# MCU.net
KiCad netlist of a schematic drawn in Altium Designer
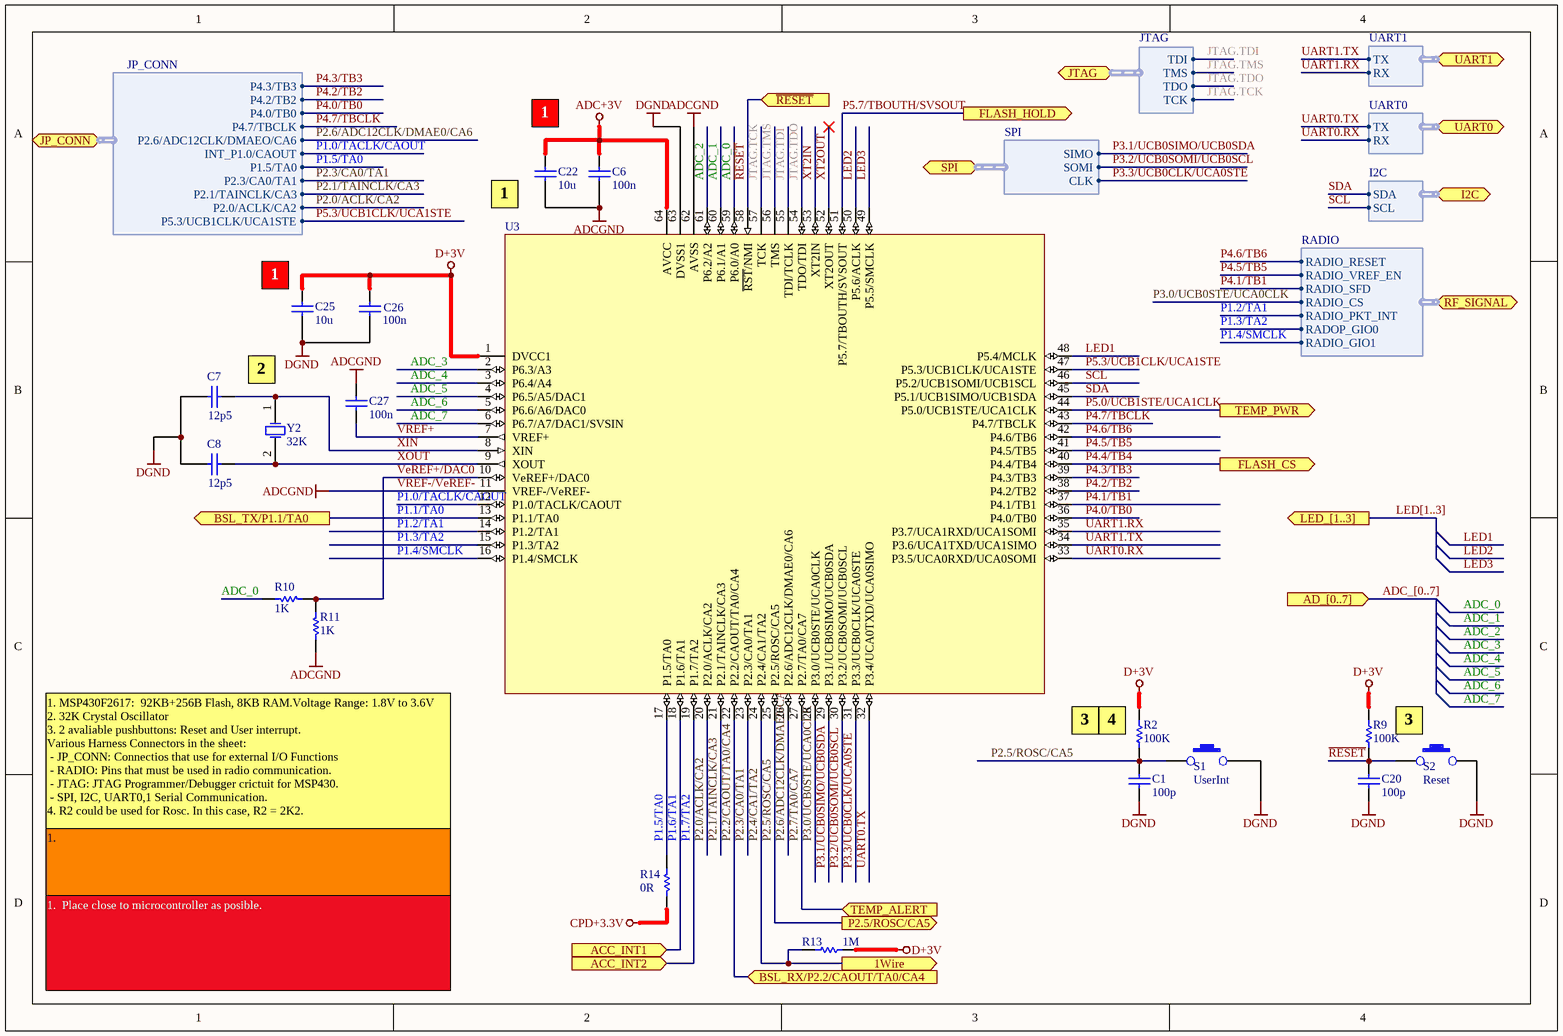
[diagram p0: MCU.SchDoc]

(export (version "E")
  (design (tool "Eeschema 10.0.6"))
  (components
    (comp (ref "C1")
      (value "100p")
      (footprint "CC-0402-AL")
      (description "Capacitor (Semiconductor SIM Model)")
      (fields (field (name "Comment") "Cap Semi"))
      (libsource (lib "Z1_Project") (part "Cap Semi"))
    )
    (comp (ref "C6")
      (value "100n")
      (footprint "CC-0402-AL")
      (description "Capacitor (Semiconductor SIM Model)")
      (fields (field (name "Comment") "Cap Semi"))
      (libsource (lib "Z1_Project") (part "Cap Semi"))
    )
    (comp (ref "C7")
      (value "12p5")
      (footprint "CC-0402-AL")
      (description "Capacitor (Semiconductor SIM Model)")
      (fields (field (name "Comment") "Cap Semi"))
      (libsource (lib "Z1_Project") (part "Cap Semi"))
    )
    (comp (ref "C8")
      (value "12p5")
      (footprint "CC-0402-AL")
      (description "Capacitor (Semiconductor SIM Model)")
      (fields (field (name "Comment") "Cap Semi"))
      (libsource (lib "Z1_Project") (part "Cap Semi"))
    )
    (comp (ref "C20")
      (value "100p")
      (footprint "CC-0402-AL")
      (description "Capacitor (Semiconductor SIM Model)")
      (fields (field (name "Comment") "Cap Semi"))
      (libsource (lib "Z1_Project") (part "Cap Semi"))
    )
    (comp (ref "C22")
      (value "10u")
      (footprint "CC1608-0603")
      (description "CAP CER 10UF 6.3V X5R 0603")
      (fields (field (name "Comment") "Cap Semi"))
      (libsource (lib "Z1_Project") (part "Cap Semi"))
    )
    (comp (ref "C25")
      (value "10u")
      (footprint "CC1608-0603")
      (description "CAP CER 10UF 6.3V X5R 0603")
      (fields (field (name "Comment") "Cap Semi"))
      (libsource (lib "Z1_Project") (part "Cap Semi"))
    )
    (comp (ref "C26")
      (value "100n")
      (footprint "CC-0402-AL")
      (description "Capacitor (Semiconductor SIM Model)")
      (fields (field (name "Comment") "Cap Semi"))
      (libsource (lib "Z1_Project") (part "Cap Semi"))
    )
    (comp (ref "C27")
      (value "100n")
      (footprint "CC-0402-AL")
      (description "Capacitor (Semiconductor SIM Model)")
      (fields (field (name "Comment") "Cap Semi"))
      (libsource (lib "Z1_Project") (part "Cap Semi"))
    )
    (comp (ref "R2")
      (value "100K")
      (footprint "CR1005-0402")
      (description "Semiconductor Resistor")
      (fields (field (name "MANUFACTURER") "Generic Components") (field (name "Comment") "Res Semi"))
      (libsource (lib "Z1_Project") (part "Res Semi"))
    )
    (comp (ref "R9")
      (value "100K")
      (footprint "CR-0402-AL")
      (description "Semiconductor Resistor")
      (fields (field (name "Comment") "Res Semi"))
      (libsource (lib "Z1_Project") (part "Res Semi"))
    )
    (comp (ref "R10")
      (value "1K")
      (footprint "CR-0402-AL")
      (description "Semiconductor Resistor")
      (fields (field (name "Comment") "Res Semi"))
      (libsource (lib "Z1_Project") (part "Res Semi"))
    )
    (comp (ref "R11")
      (value "1K")
      (footprint "CR-0402-AL")
      (description "Semiconductor Resistor")
      (fields (field (name "Comment") "Res Semi"))
      (libsource (lib "Z1_Project") (part "Res Semi"))
    )
    (comp (ref "R13")
      (value "1M")
      (footprint "CR-0402-AL")
      (description "Semiconductor Resistor")
      (fields (field (name "Comment") "Res Semi"))
      (libsource (lib "Z1_Project") (part "Res Semi"))
    )
    (comp (ref "R14")
      (value "0R")
      (footprint "CR-0402-AL")
      (description "Semiconductor Resistor")
      (fields (field (name "Comment") "Res Semi"))
      (libsource (lib "Z1_Project") (part "Res Semi"))
    )
    (comp (ref "S1")
      (value "UserInt")
      (footprint "B3U-1000P")
      (description "Ultra-small Tactile Switch")
      (libsource (lib "Z1_Project") (part "B3U-1000P"))
    )
    (comp (ref "S2")
      (value "Reset")
      (footprint "B3U-1000P")
      (description "Ultra-small Tactile Switch")
      (libsource (lib "Z1_Project") (part "B3U-1000P"))
    )
    (comp (ref "U3")
      (value "MSP430F2617TPMR")
      (footprint "F-QFP10x10-G64/N")
      (description "MSP430F2617TPMR MICROCONTROLLER")
      (libsource (lib "Z1_Project") (part "MSP430F2617TPMR"))
    )
    (comp (ref "Y2")
      (value "32K")
      (footprint "ABS07-32.768KHZ-7-T")
      (description "Crystal Oscillator")
      (fields (field (name "MANUFACTURER") "Generic Components"))
      (libsource (lib "Z1_Project") (part "XTAL"))
    )
  )
  (nets
    (net (code "8") (name "/ADC_0") (class "Default")
      (node (ref "R10") (pin "2") (pinfunction "2_2") (pintype "passive"))
      (node (ref "U3") (pin "59") (pinfunction "P6.0/A0_59") (pintype "bidirectional"))
    )
    (net (code "9") (name "/ADC_1") (class "Default")
      (node (ref "U3") (pin "60") (pinfunction "P6.1/A1_60") (pintype "bidirectional"))
    )
    (net (code "10") (name "/ADC_2") (class "Default")
      (node (ref "U3") (pin "61") (pinfunction "P6.2/A2_61") (pintype "bidirectional"))
    )
    (net (code "11") (name "/ADC_3") (class "Default")
      (node (ref "U3") (pin "2") (pinfunction "P6.3/A3_2") (pintype "bidirectional"))
    )
    (net (code "12") (name "/ADC_4") (class "Default")
      (node (ref "U3") (pin "3") (pinfunction "P6.4/A4_3") (pintype "bidirectional"))
    )
    (net (code "13") (name "/ADC_5") (class "Default")
      (node (ref "U3") (pin "4") (pinfunction "P6.5/A5/DAC1_4") (pintype "bidirectional"))
    )
    (net (code "14") (name "/ADC_6") (class "Default")
      (node (ref "U3") (pin "5") (pinfunction "P6.6/A6/DAC0_5") (pintype "bidirectional"))
    )
    (net (code "15") (name "/ADC_7") (class "Default")
      (node (ref "U3") (pin "6") (pinfunction "P6.7/A7/DAC1/SVSIN_6") (pintype "bidirectional"))
    )
    (net (code "17") (name "/JTAG.TCK") (class "Default")
      (node (ref "U3") (pin "57") (pinfunction "TCK_57") (pintype "passive"))
    )
    (net (code "18") (name "/JTAG.TDI") (class "Default")
      (node (ref "U3") (pin "55") (pinfunction "TDI/TCLK_55") (pintype "passive"))
    )
    (net (code "19") (name "/JTAG.TDO") (class "Default")
      (node (ref "U3") (pin "54") (pinfunction "TDO/TDI_54") (pintype "bidirectional"))
    )
    (net (code "20") (name "/JTAG.TMS") (class "Default")
      (node (ref "U3") (pin "56") (pinfunction "TMS_56") (pintype "passive"))
    )
    (net (code "21") (name "/LED1") (class "Default")
      (node (ref "U3") (pin "48") (pinfunction "P5.4/MCLK_48") (pintype "bidirectional"))
    )
    (net (code "22") (name "/LED2") (class "Default")
      (node (ref "U3") (pin "50") (pinfunction "P5.6/ACLK_50") (pintype "bidirectional"))
    )
    (net (code "23") (name "/LED3") (class "Default")
      (node (ref "U3") (pin "49") (pinfunction "P5.5/SMCLK_49") (pintype "bidirectional"))
    )
    (net (code "25") (name "/P1.0{slash}TACLK{slash}CAOUT") (class "Default")
      (node (ref "U3") (pin "12") (pinfunction "P1.0/TACLK/CAOUT_12") (pintype "bidirectional"))
    )
    (net (code "26") (name "/P1.1{slash}TA0") (class "Default")
      (node (ref "U3") (pin "13") (pinfunction "P1.1/TA0_13") (pintype "bidirectional"))
    )
    (net (code "27") (name "/P1.2{slash}TA1") (class "Default")
      (node (ref "U3") (pin "14") (pinfunction "P1.2/TA1_14") (pintype "bidirectional"))
    )
    (net (code "28") (name "/P1.3{slash}TA2") (class "Default")
      (node (ref "U3") (pin "15") (pinfunction "P1.3/TA2_15") (pintype "bidirectional"))
    )
    (net (code "29") (name "/P1.4{slash}SMCLK") (class "Default")
      (node (ref "U3") (pin "16") (pinfunction "P1.4/SMCLK_16") (pintype "bidirectional"))
    )
    (net (code "30") (name "/P1.5{slash}TA0") (class "Default")
      (node (ref "R14") (pin "2") (pinfunction "2_2") (pintype "passive"))
      (node (ref "U3") (pin "17") (pinfunction "P1.5/TA0_17") (pintype "bidirectional"))
    )
    (net (code "31") (name "/P1.6{slash}TA1") (class "Default")
      (node (ref "U3") (pin "18") (pinfunction "P1.6/TA1_18") (pintype "bidirectional"))
    )
    (net (code "32") (name "/P1.7{slash}TA2") (class "Default")
      (node (ref "U3") (pin "19") (pinfunction "P1.7/TA2_19") (pintype "bidirectional"))
    )
    (net (code "33") (name "/P2.0{slash}ACLK{slash}CA2") (class "Default")
      (node (ref "U3") (pin "20") (pinfunction "P2.0/ACLK/CA2_20") (pintype "bidirectional"))
    )
    (net (code "34") (name "/P2.1{slash}TAINCLK{slash}CA3") (class "Default")
      (node (ref "U3") (pin "21") (pinfunction "P2.1/TAINCLK/CA3_21") (pintype "bidirectional"))
    )
    (net (code "35") (name "/P2.2{slash}CAOUT{slash}TA0{slash}CA4") (class "Default")
      (node (ref "U3") (pin "22") (pinfunction "P2.2/CAOUT/TA0/CA4_22") (pintype "bidirectional"))
    )
    (net (code "36") (name "/P2.3{slash}CA0{slash}TA1") (class "Default")
      (node (ref "U3") (pin "23") (pinfunction "P2.3/CA0/TA1_23") (pintype "bidirectional"))
    )
    (net (code "37") (name "/P2.4{slash}CA1{slash}TA2") (class "Default")
      (node (ref "R13") (pin "2") (pinfunction "2_2") (pintype "passive"))
      (node (ref "U3") (pin "24") (pinfunction "P2.4/CA1/TA2_24") (pintype "bidirectional"))
    )
    (net (code "38") (name "/P2.5{slash}ROSC{slash}CA5") (class "Default")
      (node (ref "C1") (pin "1") (pinfunction "1_1") (pintype "passive"))
      (node (ref "R2") (pin "2") (pinfunction "2_2") (pintype "passive"))
      (node (ref "S1") (pin "1") (pinfunction "1_1") (pintype "passive"))
      (node (ref "U3") (pin "25") (pinfunction "P2.5/ROSC/CA5_25") (pintype "bidirectional"))
    )
    (net (code "39") (name "/P2.6{slash}ADC12CLK{slash}DMAE0{slash}CA6") (class "Default")
      (node (ref "U3") (pin "26") (pinfunction "P2.6/ADC12CLK/DMAE0/CA6_26") (pintype "bidirectional"))
    )
    (net (code "40") (name "/P2.7{slash}TA0{slash}CA7") (class "Default")
      (node (ref "U3") (pin "27") (pinfunction "P2.7/TA0/CA7_27") (pintype "bidirectional"))
    )
    (net (code "41") (name "/P3.0{slash}UCB0STE{slash}UCA0CLK") (class "Default")
      (node (ref "U3") (pin "28") (pinfunction "P3.0/UCB0STE/UCA0CLK_28") (pintype "bidirectional"))
    )
    (net (code "42") (name "/P3.1{slash}UCB0SIMO{slash}UCB0SDA") (class "Default")
      (node (ref "U3") (pin "29") (pinfunction "P3.1/UCB0SIMO/UCB0SDA_29") (pintype "bidirectional"))
    )
    (net (code "43") (name "/P3.2{slash}UCB0SOMI{slash}UCB0SCL") (class "Default")
      (node (ref "U3") (pin "30") (pinfunction "P3.2/UCB0SOMI/UCB0SCL_30") (pintype "bidirectional"))
    )
    (net (code "44") (name "/P3.3{slash}UCB0CLK{slash}UCA0STE") (class "Default")
      (node (ref "U3") (pin "31") (pinfunction "P3.3/UCB0CLK/UCA0STE_31") (pintype "bidirectional"))
    )
    (net (code "45") (name "/P4.0{slash}TB0") (class "Default")
      (node (ref "U3") (pin "36") (pinfunction "P4.0/TB0_36") (pintype "bidirectional"))
    )
    (net (code "46") (name "/P4.1{slash}TB1") (class "Default")
      (node (ref "U3") (pin "37") (pinfunction "P4.1/TB1_37") (pintype "bidirectional"))
    )
    (net (code "47") (name "/P4.2{slash}TB2") (class "Default")
      (node (ref "U3") (pin "38") (pinfunction "P4.2/TB2_38") (pintype "bidirectional"))
    )
    (net (code "48") (name "/P4.3{slash}TB3") (class "Default")
      (node (ref "U3") (pin "39") (pinfunction "P4.3/TB3_39") (pintype "bidirectional"))
    )
    (net (code "49") (name "/P4.4{slash}TB4") (class "Default")
      (node (ref "U3") (pin "40") (pinfunction "P4.4/TB4_40") (pintype "bidirectional"))
    )
    (net (code "50") (name "/P4.5{slash}TB5") (class "Default")
      (node (ref "U3") (pin "41") (pinfunction "P4.5/TB5_41") (pintype "bidirectional"))
    )
    (net (code "51") (name "/P4.6{slash}TB6") (class "Default")
      (node (ref "U3") (pin "42") (pinfunction "P4.6/TB6_42") (pintype "bidirectional"))
    )
    (net (code "52") (name "/P4.7{slash}TBCLK") (class "Default")
      (node (ref "U3") (pin "43") (pinfunction "P4.7/TBCLK_43") (pintype "bidirectional"))
    )
    (net (code "53") (name "/P5.0{slash}UCB1STE{slash}UCA1CLK") (class "Default")
      (node (ref "U3") (pin "44") (pinfunction "P5.0/UCB1STE/UCA1CLK_44") (pintype "bidirectional"))
    )
    (net (code "54") (name "/P5.3{slash}UCB1CLK{slash}UCA1STE") (class "Default")
      (node (ref "U3") (pin "47") (pinfunction "P5.3/UCB1CLK/UCA1STE_47") (pintype "bidirectional"))
    )
    (net (code "55") (name "/P5.7{slash}TBOUTH{slash}SVSOUT") (class "Default")
      (node (ref "U3") (pin "51") (pinfunction "P5.7/TBOUTH/SVSOUT_51") (pintype "bidirectional"))
    )
    (net (code "56") (name "/SCL") (class "Default")
      (node (ref "U3") (pin "46") (pinfunction "P5.2/UCB1SOMI/UCB1SCL_46") (pintype "bidirectional"))
    )
    (net (code "57") (name "/SDA") (class "Default")
      (node (ref "U3") (pin "45") (pinfunction "P5.1/UCB1SIMO/UCB1SDA_45") (pintype "bidirectional"))
    )
    (net (code "58") (name "/UART0.RX") (class "Default")
      (node (ref "U3") (pin "33") (pinfunction "P3.5/UCA0RXD/UCA0SOMI_33") (pintype "bidirectional"))
    )
    (net (code "59") (name "/UART0.TX") (class "Default")
      (node (ref "U3") (pin "32") (pinfunction "P3.4/UCA0TXD/UCA0SIMO_32") (pintype "bidirectional"))
    )
    (net (code "60") (name "/UART1.RX") (class "Default")
      (node (ref "U3") (pin "35") (pinfunction "P3.7/UCA1RXD/UCA1SOMI_35") (pintype "bidirectional"))
    )
    (net (code "61") (name "/UART1.TX") (class "Default")
      (node (ref "U3") (pin "34") (pinfunction "P3.6/UCA1TXD/UCA1SIMO_34") (pintype "bidirectional"))
    )
    (net (code "62") (name "/VREF+") (class "Default")
      (node (ref "C27") (pin "2") (pinfunction "2_2") (pintype "passive"))
      (node (ref "U3") (pin "7") (pinfunction "VREF+_7") (pintype "output"))
    )
    (net (code "63") (name "/VeREF+{slash}DAC0") (class "Default")
      (node (ref "R10") (pin "1") (pinfunction "1_1") (pintype "passive"))
      (node (ref "R11") (pin "2") (pinfunction "2_2") (pintype "passive"))
      (node (ref "U3") (pin "10") (pinfunction "VeREF+/DAC0_10") (pintype "bidirectional"))
    )
    (net (code "64") (name "/XIN") (class "Default")
      (node (ref "C7") (pin "2") (pinfunction "2_2") (pintype "passive"))
      (node (ref "U3") (pin "8") (pinfunction "XIN_8") (pintype "input"))
      (node (ref "Y2") (pin "1") (pinfunction "OSC1_1") (pintype "passive"))
    )
    (net (code "65") (name "/XOUT") (class "Default")
      (node (ref "C8") (pin "2") (pinfunction "2_2") (pintype "passive"))
      (node (ref "U3") (pin "9") (pinfunction "XOUT_9") (pintype "output"))
      (node (ref "Y2") (pin "2") (pinfunction "OSC2_2") (pintype "passive"))
    )
    (net (code "66") (name "/XT2IN") (class "Default")
      (node (ref "U3") (pin "53") (pinfunction "XT2IN_53") (pintype "bidirectional"))
    )
    (net (code "67") (name "/XT2OUT") (class "Default")
      (node (ref "U3") (pin "52") (pinfunction "XT2OUT_52") (pintype "bidirectional+no_connect"))
    )
    (net (code "75") (name "/~{RESET}") (class "Default")
      (node (ref "C20") (pin "1") (pinfunction "1_1") (pintype "passive"))
      (node (ref "R9") (pin "1") (pinfunction "1_1") (pintype "passive"))
      (node (ref "S2") (pin "1") (pinfunction "1_1") (pintype "passive"))
      (node (ref "U3") (pin "58") (pinfunction "~{RST}/NMI_58") (pintype "input"))
    )
    (net (code "76") (name "ADC+3V") (class "Default")
      (node (ref "C22") (pin "1") (pinfunction "1_1") (pintype "passive"))
      (node (ref "C6") (pin "1") (pinfunction "1_1") (pintype "passive"))
      (node (ref "U3") (pin "64") (pinfunction "AVCC_64") (pintype "power_in"))
    )
    (net (code "77") (name "ADCGND") (class "Default")
      (node (ref "C22") (pin "2") (pinfunction "2_2") (pintype "passive"))
      (node (ref "C27") (pin "1") (pinfunction "1_1") (pintype "passive"))
      (node (ref "C6") (pin "2") (pinfunction "2_2") (pintype "passive"))
      (node (ref "R11") (pin "1") (pinfunction "1_1") (pintype "passive"))
      (node (ref "U3") (pin "11") (pinfunction "VREF-/VeREF-_11") (pintype "power_in"))
      (node (ref "U3") (pin "62") (pinfunction "AVSS_62") (pintype "power_in"))
    )
    (net (code "78") (name "CPD+3.3V") (class "Default")
      (node (ref "R14") (pin "1") (pinfunction "1_1") (pintype "passive"))
    )
    (net (code "79") (name "D+3V") (class "Default")
      (node (ref "C25") (pin "1") (pinfunction "1_1") (pintype "passive"))
      (node (ref "C26") (pin "1") (pinfunction "1_1") (pintype "passive"))
      (node (ref "R13") (pin "1") (pinfunction "1_1") (pintype "passive"))
      (node (ref "R2") (pin "1") (pinfunction "1_1") (pintype "passive"))
      (node (ref "R9") (pin "2") (pinfunction "2_2") (pintype "passive"))
      (node (ref "U3") (pin "1") (pinfunction "DVCC1_1") (pintype "power_in"))
    )
    (net (code "80") (name "DGND") (class "Default")
      (node (ref "C1") (pin "2") (pinfunction "2_2") (pintype "passive"))
      (node (ref "C20") (pin "2") (pinfunction "2_2") (pintype "passive"))
      (node (ref "C25") (pin "2") (pinfunction "2_2") (pintype "passive"))
      (node (ref "C26") (pin "2") (pinfunction "2_2") (pintype "passive"))
      (node (ref "C7") (pin "1") (pinfunction "1_1") (pintype "passive"))
      (node (ref "C8") (pin "1") (pinfunction "1_1") (pintype "passive"))
      (node (ref "S1") (pin "2") (pinfunction "2_2") (pintype "passive"))
      (node (ref "S2") (pin "2") (pinfunction "2_2") (pintype "passive"))
      (node (ref "U3") (pin "63") (pinfunction "DVSS1_63") (pintype "power_in"))
    )
  )
)
